# servodengen.net
KiCad netlist of a schematic drawn in EAGLE
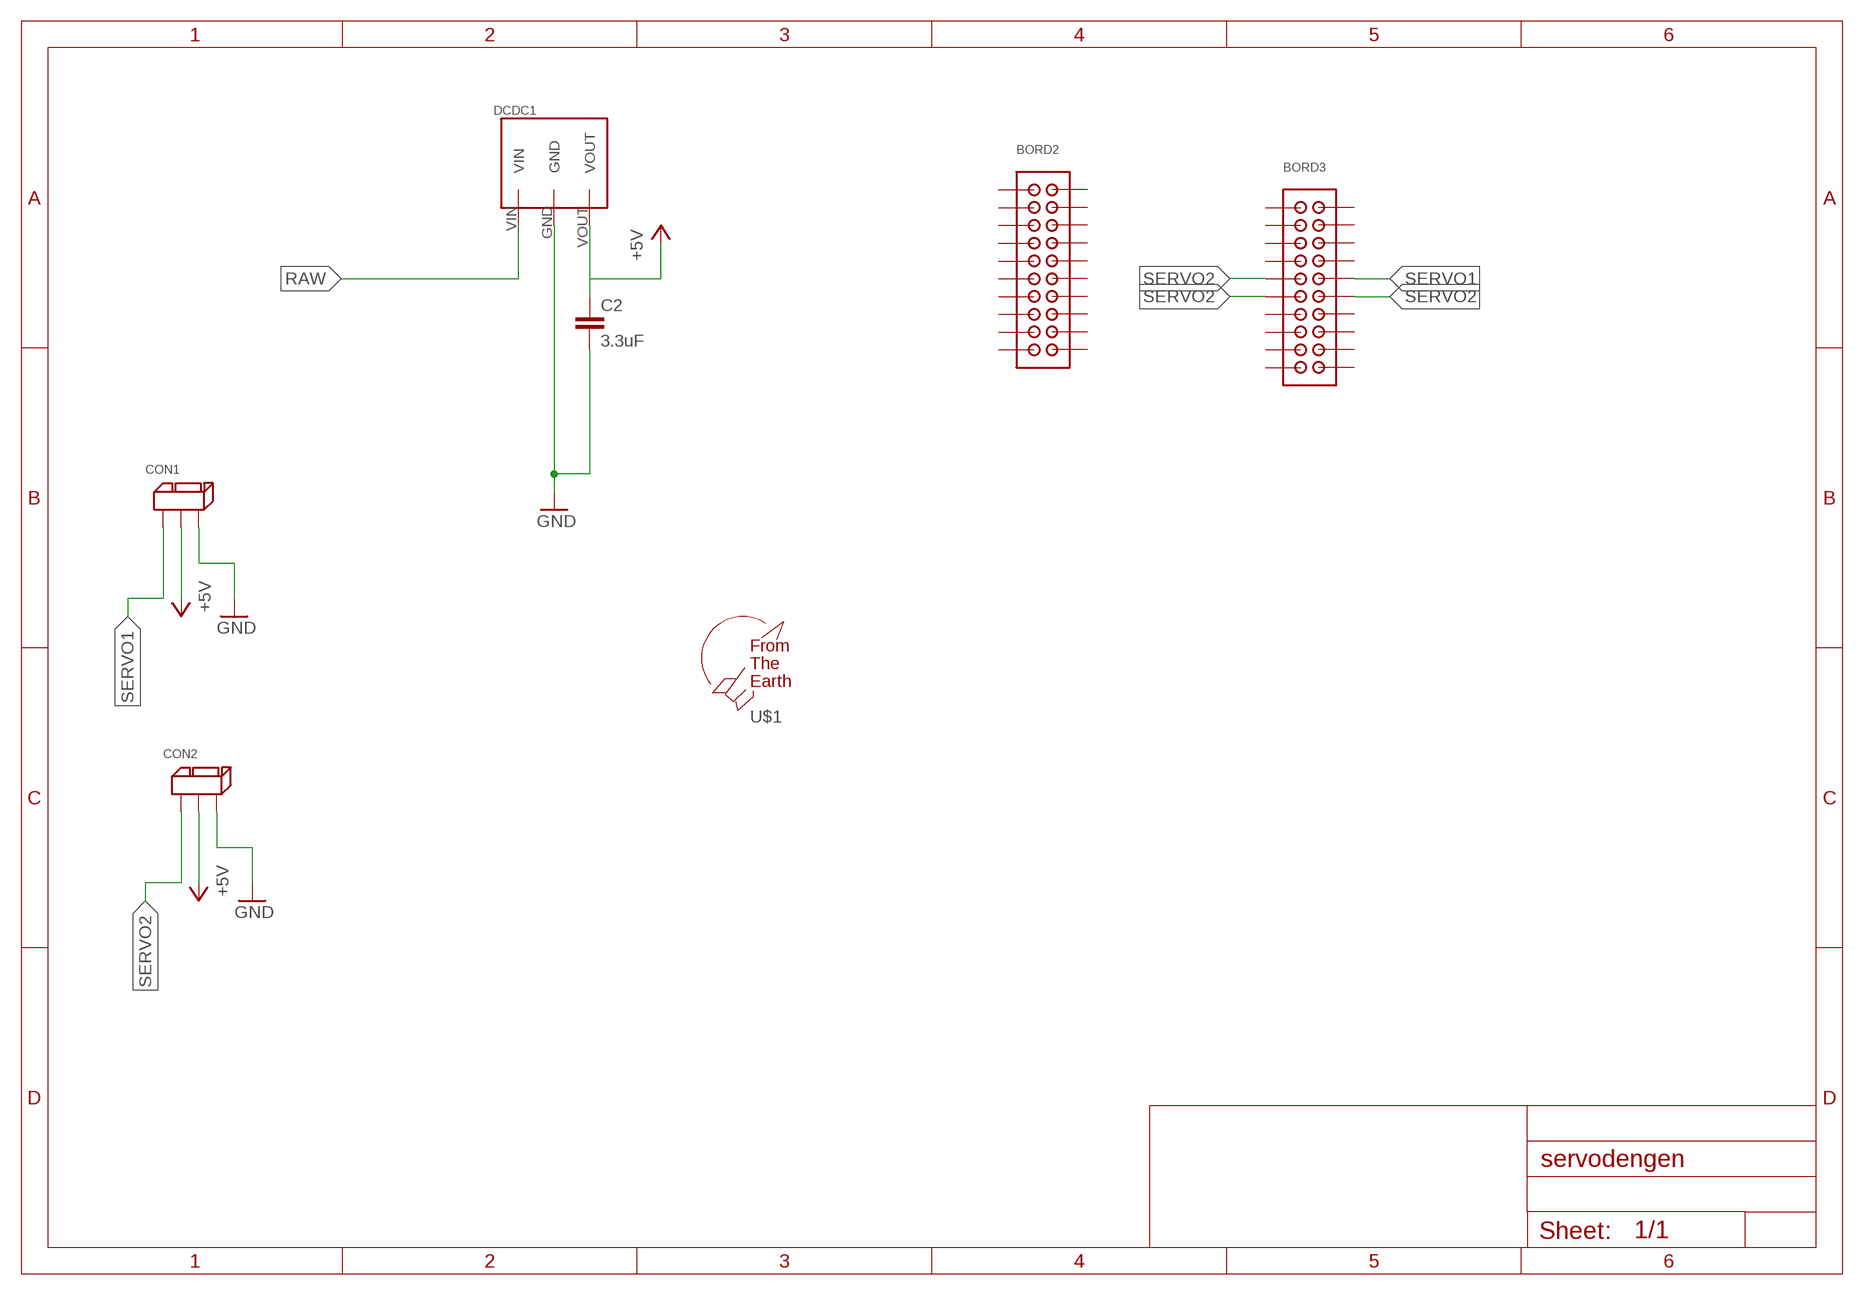
[diagram p0: schematic, sheet 1]

(export (version "E")
  (design (tool "Eeschema 10.0.6"))
  (components
    (comp (ref "BORD2")
      (value "2X10")
      (footprint "eagle-import:2X10")
      (libsource (lib "eagle-import") (part "2X10"))
    )
    (comp (ref "BORD3")
      (value "2X10")
      (footprint "eagle-import:2X10")
      (libsource (lib "eagle-import") (part "2X10"))
    )
    (comp (ref "C2")
      (value "3.3uF")
      (footprint "eagle-import:C025-024X044")
      (libsource (lib "eagle-import") (part "C-EU025-024X044"))
    )
    (comp (ref "CON1")
      (value "3PIN")
      (footprint "eagle-import:3PIN")
      (libsource (lib "eagle-import") (part "3PIN"))
    )
    (comp (ref "CON2")
      (value "3PIN")
      (footprint "eagle-import:3PIN")
      (libsource (lib "eagle-import") (part "3PIN"))
    )
    (comp (ref "DCDC1")
      (value "5V1A_M78AR05-1")
      (footprint "eagle-import:5V1A_M78AR05-1")
      (libsource (lib "eagle-import") (part "5V1A_M78AR05-1"))
    )
    (comp (ref "U$1")
      (value "F.T.E.LOGO")
      (footprint "eagle-import:LOGO")
      (libsource (lib "eagle-import") (part "F.T.E.LOGO"))
    )
  )
  (nets
    (net (code "1") (name "+5V") (class "Default")
      (node (ref "C2") (pin "1") (pinfunction "1_1") (pintype "passive"))
      (node (ref "CON1") (pin "P$2") (pinfunction "P$2_P$2") (pintype "bidirectional"))
      (node (ref "CON2") (pin "P$2") (pinfunction "P$2_P$2") (pintype "bidirectional"))
      (node (ref "DCDC1") (pin "VOUT") (pinfunction "VOUT_VOUT") (pintype "bidirectional"))
    )
    (net (code "2") (name "GND") (class "Default")
      (node (ref "C2") (pin "2") (pinfunction "2_2") (pintype "passive"))
      (node (ref "CON1") (pin "P$3") (pinfunction "P$3_P$3") (pintype "bidirectional"))
      (node (ref "CON2") (pin "P$3") (pinfunction "P$3_P$3") (pintype "bidirectional"))
      (node (ref "DCDC1") (pin "GND") (pinfunction "GND_GND") (pintype "bidirectional"))
    )
    (net (code "3") (name "RAW") (class "Default")
      (node (ref "DCDC1") (pin "VIN") (pinfunction "VIN_VIN") (pintype "bidirectional"))
    )
    (net (code "4") (name "SERVO1") (class "Default")
      (node (ref "BORD3") (pin "P$10") (pinfunction "P$10_P$10") (pintype "bidirectional"))
      (node (ref "CON1") (pin "P$1") (pinfunction "P$1_P$1") (pintype "bidirectional"))
    )
    (net (code "5") (name "SERVO2") (class "Default")
      (node (ref "BORD3") (pin "P$11") (pinfunction "P$11_P$11") (pintype "bidirectional"))
      (node (ref "BORD3") (pin "P$12") (pinfunction "P$12_P$12") (pintype "bidirectional"))
      (node (ref "BORD3") (pin "P$9") (pinfunction "P$9_P$9") (pintype "bidirectional"))
      (node (ref "CON2") (pin "P$1") (pinfunction "P$1_P$1") (pintype "bidirectional"))
    )
    (net (code "6") (name "unconnected-(BORD2-PadP$1)") (class "Default")
      (node (ref "BORD2") (pin "P$1") (pinfunction "P$1_P$1") (pintype "bidirectional"))
    )
    (net (code "7") (name "unconnected-(BORD2-PadP$2)") (class "Default")
      (node (ref "BORD2") (pin "P$2") (pinfunction "P$2_P$2") (pintype "bidirectional"))
    )
    (net (code "8") (name "unconnected-(BORD2-PadP$3)") (class "Default")
      (node (ref "BORD2") (pin "P$3") (pinfunction "P$3_P$3") (pintype "bidirectional"))
    )
    (net (code "9") (name "unconnected-(BORD2-PadP$4)") (class "Default")
      (node (ref "BORD2") (pin "P$4") (pinfunction "P$4_P$4") (pintype "bidirectional"))
    )
    (net (code "10") (name "unconnected-(BORD2-PadP$5)") (class "Default")
      (node (ref "BORD2") (pin "P$5") (pinfunction "P$5_P$5") (pintype "bidirectional"))
    )
    (net (code "11") (name "unconnected-(BORD2-PadP$6)") (class "Default")
      (node (ref "BORD2") (pin "P$6") (pinfunction "P$6_P$6") (pintype "bidirectional"))
    )
    (net (code "12") (name "unconnected-(BORD2-PadP$7)") (class "Default")
      (node (ref "BORD2") (pin "P$7") (pinfunction "P$7_P$7") (pintype "bidirectional"))
    )
    (net (code "13") (name "unconnected-(BORD2-PadP$8)") (class "Default")
      (node (ref "BORD2") (pin "P$8") (pinfunction "P$8_P$8") (pintype "bidirectional"))
    )
    (net (code "14") (name "unconnected-(BORD2-PadP$9)") (class "Default")
      (node (ref "BORD2") (pin "P$9") (pinfunction "P$9_P$9") (pintype "bidirectional"))
    )
    (net (code "15") (name "unconnected-(BORD2-PadP$10)") (class "Default")
      (node (ref "BORD2") (pin "P$10") (pinfunction "P$10_P$10") (pintype "bidirectional"))
    )
    (net (code "16") (name "unconnected-(BORD2-PadP$11)") (class "Default")
      (node (ref "BORD2") (pin "P$11") (pinfunction "P$11_P$11") (pintype "bidirectional"))
    )
    (net (code "17") (name "unconnected-(BORD2-PadP$12)") (class "Default")
      (node (ref "BORD2") (pin "P$12") (pinfunction "P$12_P$12") (pintype "bidirectional"))
    )
    (net (code "18") (name "unconnected-(BORD2-PadP$13)") (class "Default")
      (node (ref "BORD2") (pin "P$13") (pinfunction "P$13_P$13") (pintype "bidirectional"))
    )
    (net (code "19") (name "unconnected-(BORD2-PadP$14)") (class "Default")
      (node (ref "BORD2") (pin "P$14") (pinfunction "P$14_P$14") (pintype "bidirectional"))
    )
    (net (code "20") (name "unconnected-(BORD2-PadP$15)") (class "Default")
      (node (ref "BORD2") (pin "P$15") (pinfunction "P$15_P$15") (pintype "bidirectional"))
    )
    (net (code "21") (name "unconnected-(BORD2-PadP$16)") (class "Default")
      (node (ref "BORD2") (pin "P$16") (pinfunction "P$16_P$16") (pintype "bidirectional"))
    )
    (net (code "22") (name "unconnected-(BORD2-PadP$17)") (class "Default")
      (node (ref "BORD2") (pin "P$17") (pinfunction "P$17_P$17") (pintype "bidirectional"))
    )
    (net (code "23") (name "unconnected-(BORD2-PadP$18)") (class "Default")
      (node (ref "BORD2") (pin "P$18") (pinfunction "P$18_P$18") (pintype "bidirectional"))
    )
    (net (code "24") (name "unconnected-(BORD2-PadP$19)") (class "Default")
      (node (ref "BORD2") (pin "P$19") (pinfunction "P$19_P$19") (pintype "bidirectional"))
    )
    (net (code "25") (name "unconnected-(BORD2-PadP$20)") (class "Default")
      (node (ref "BORD2") (pin "P$20") (pinfunction "P$20_P$20") (pintype "bidirectional"))
    )
    (net (code "26") (name "unconnected-(BORD3-PadP$1)") (class "Default")
      (node (ref "BORD3") (pin "P$1") (pinfunction "P$1_P$1") (pintype "bidirectional"))
    )
    (net (code "27") (name "unconnected-(BORD3-PadP$2)") (class "Default")
      (node (ref "BORD3") (pin "P$2") (pinfunction "P$2_P$2") (pintype "bidirectional"))
    )
    (net (code "28") (name "unconnected-(BORD3-PadP$3)") (class "Default")
      (node (ref "BORD3") (pin "P$3") (pinfunction "P$3_P$3") (pintype "bidirectional"))
    )
    (net (code "29") (name "unconnected-(BORD3-PadP$4)") (class "Default")
      (node (ref "BORD3") (pin "P$4") (pinfunction "P$4_P$4") (pintype "bidirectional"))
    )
    (net (code "30") (name "unconnected-(BORD3-PadP$5)") (class "Default")
      (node (ref "BORD3") (pin "P$5") (pinfunction "P$5_P$5") (pintype "bidirectional"))
    )
    (net (code "31") (name "unconnected-(BORD3-PadP$6)") (class "Default")
      (node (ref "BORD3") (pin "P$6") (pinfunction "P$6_P$6") (pintype "bidirectional"))
    )
    (net (code "32") (name "unconnected-(BORD3-PadP$7)") (class "Default")
      (node (ref "BORD3") (pin "P$7") (pinfunction "P$7_P$7") (pintype "bidirectional"))
    )
    (net (code "33") (name "unconnected-(BORD3-PadP$8)") (class "Default")
      (node (ref "BORD3") (pin "P$8") (pinfunction "P$8_P$8") (pintype "bidirectional"))
    )
    (net (code "34") (name "unconnected-(BORD3-PadP$13)") (class "Default")
      (node (ref "BORD3") (pin "P$13") (pinfunction "P$13_P$13") (pintype "bidirectional"))
    )
    (net (code "35") (name "unconnected-(BORD3-PadP$14)") (class "Default")
      (node (ref "BORD3") (pin "P$14") (pinfunction "P$14_P$14") (pintype "bidirectional"))
    )
    (net (code "36") (name "unconnected-(BORD3-PadP$15)") (class "Default")
      (node (ref "BORD3") (pin "P$15") (pinfunction "P$15_P$15") (pintype "bidirectional"))
    )
    (net (code "37") (name "unconnected-(BORD3-PadP$16)") (class "Default")
      (node (ref "BORD3") (pin "P$16") (pinfunction "P$16_P$16") (pintype "bidirectional"))
    )
    (net (code "38") (name "unconnected-(BORD3-PadP$17)") (class "Default")
      (node (ref "BORD3") (pin "P$17") (pinfunction "P$17_P$17") (pintype "bidirectional"))
    )
    (net (code "39") (name "unconnected-(BORD3-PadP$18)") (class "Default")
      (node (ref "BORD3") (pin "P$18") (pinfunction "P$18_P$18") (pintype "bidirectional"))
    )
    (net (code "40") (name "unconnected-(BORD3-PadP$19)") (class "Default")
      (node (ref "BORD3") (pin "P$19") (pinfunction "P$19_P$19") (pintype "bidirectional"))
    )
    (net (code "41") (name "unconnected-(BORD3-PadP$20)") (class "Default")
      (node (ref "BORD3") (pin "P$20") (pinfunction "P$20_P$20") (pintype "bidirectional"))
    )
  )
)
